# 7thCompetition_Send.net
KiCad netlist of a schematic drawn in Altium Designer
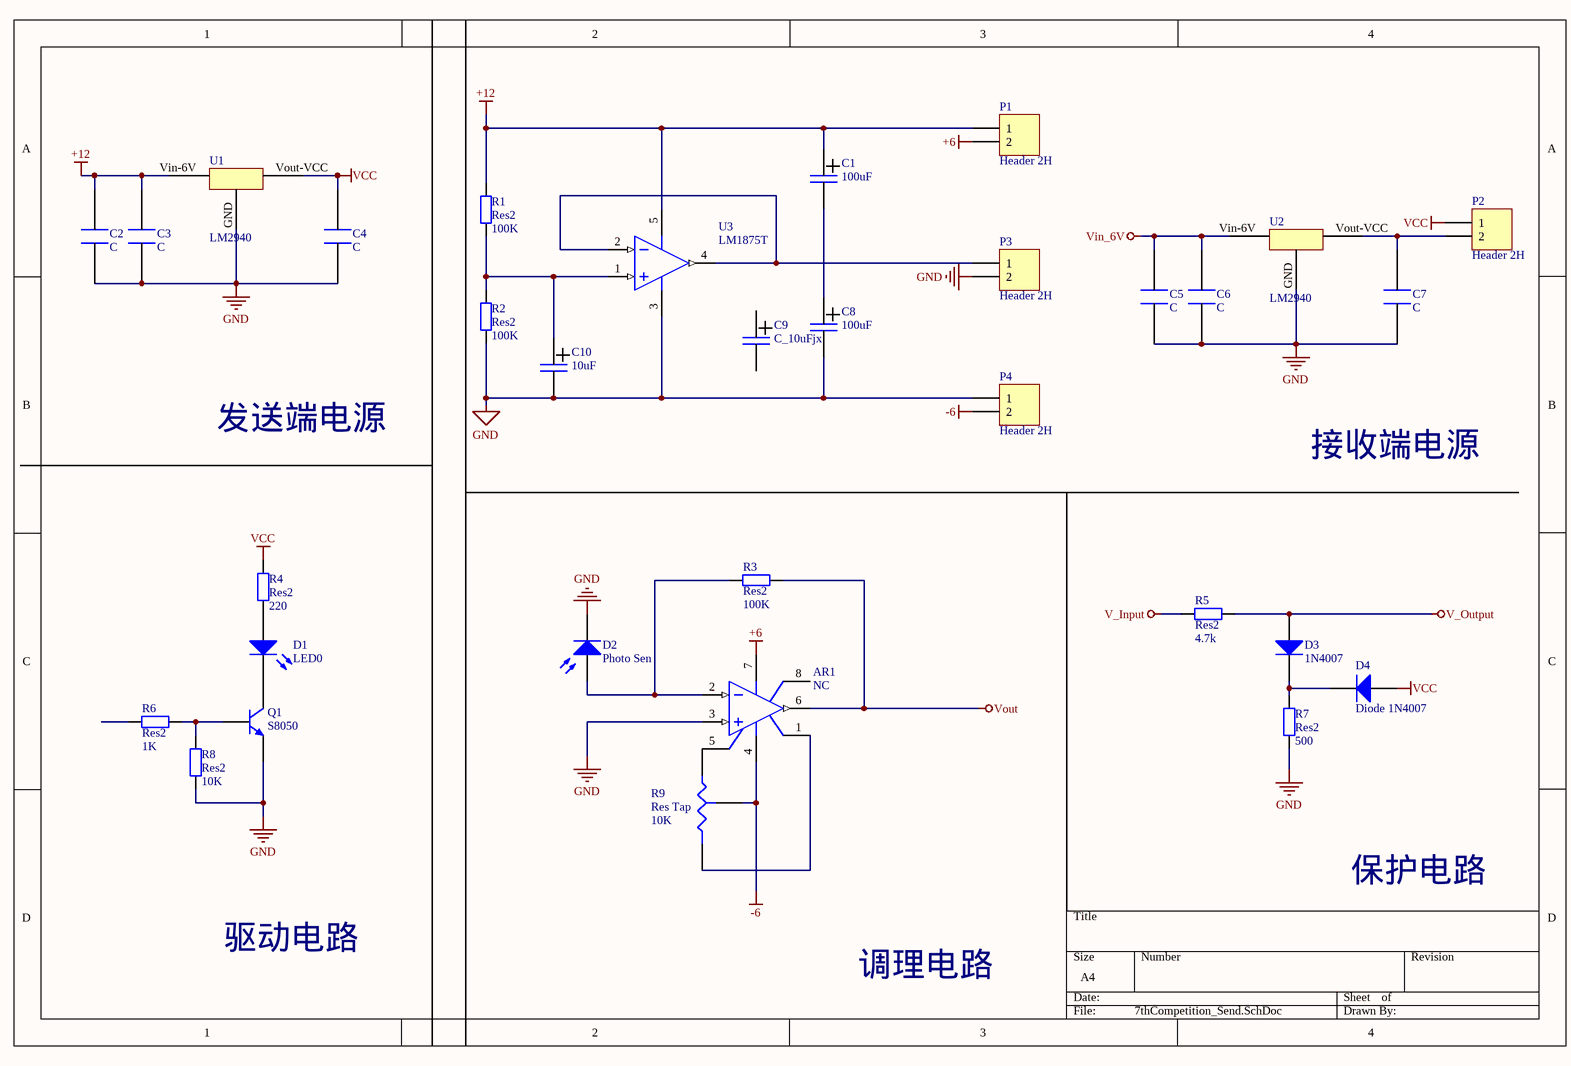
[diagram p0: 7thCompetition_Send.SchDoc]

(export (version "E")
  (design (tool "Eeschema 10.0.6"))
  (components
    (comp (ref "AR1")
      (value "NC")
      (footprint "H-08A")
      (description "FET Operational Amplifier")
      (fields (field (name "PUBLISHER") "Altium Limited"))
      (libsource (lib "Miscellaneous Devices") (part "Op Amp"))
    )
    (comp (ref "C1") (value "100uF") (footprint "C_10uFJX") (libsource (lib "常用库-Sniper") (part "C_10uFjx")))
    (comp (ref "C2") (value "C") (footprint "C") (libsource (lib "常用库-Sniper") (part "C")))
    (comp (ref "C3") (value "C") (footprint "C") (libsource (lib "常用库-Sniper") (part "C")))
    (comp (ref "C4") (value "C") (footprint "C") (libsource (lib "常用库-Sniper") (part "C")))
    (comp (ref "C5") (value "C") (footprint "C") (libsource (lib "常用库-Sniper") (part "C")))
    (comp (ref "C6") (value "C") (footprint "C") (libsource (lib "常用库-Sniper") (part "C")))
    (comp (ref "C7") (value "C") (footprint "C") (libsource (lib "常用库-Sniper") (part "C")))
    (comp (ref "C8") (value "100uF") (footprint "C_10uFJX") (libsource (lib "常用库-Sniper") (part "C_10uFjx")))
    (comp (ref "C9")
      (value "C_10uFjx")
      (footprint "C_10uFJX")
      (libsource (lib "常用库-Sniper") (part "C_10uFjx"))
    )
    (comp (ref "C10") (value "10uF") (footprint "C_10uFJX") (libsource (lib "常用库-Sniper") (part "C_10uFjx")))
    (comp (ref "D1")
      (value "LED0")
      (footprint "LED-0")
      (description "Typical INFRARED GaAs LED")
      (fields (field (name "PUBLISHER") "Altium Limited"))
      (libsource (lib "Miscellaneous Devices") (part "LED0"))
    )
    (comp (ref "D2")
      (value "Photo Sen")
      (footprint "PIN2")
      (description "Photosensitive Diode")
      (fields (field (name "PUBLISHER") "Altium Limited"))
      (libsource (lib "Miscellaneous Devices") (part "Photo Sen"))
    )
    (comp (ref "D3")
      (value "1N4007")
      (footprint "DO-41")
      (description "1 Amp General Purpose Rectifier")
      (fields (field (name "PUBLISHER") "Altium Limited"))
      (libsource (lib "Miscellaneous Devices") (part "Diode 1N4007"))
    )
    (comp (ref "D4")
      (value "Diode 1N4007")
      (footprint "DO-41")
      (description "1 Amp General Purpose Rectifier")
      (fields (field (name "PUBLISHER") "Altium Limited"))
      (libsource (lib "Miscellaneous Devices") (part "Diode 1N4007"))
    )
    (comp (ref "P1")
      (value "Header 2H")
      (footprint "HDR1X2H")
      (description "Header, 2-Pin, Right Angle")
      (fields (field (name "PUBLISHER") "Altium Limited"))
      (libsource (lib "Miscellaneous Connectors") (part "Header 2H"))
    )
    (comp (ref "P2")
      (value "Header 2H")
      (footprint "HDR1X2H")
      (description "Header, 2-Pin, Right Angle")
      (fields (field (name "PUBLISHER") "Altium Limited"))
      (libsource (lib "Miscellaneous Connectors") (part "Header 2H"))
    )
    (comp (ref "P3")
      (value "Header 2H")
      (footprint "HDR1X2H")
      (description "Header, 2-Pin, Right Angle")
      (fields (field (name "PUBLISHER") "Altium Limited"))
      (libsource (lib "Miscellaneous Connectors") (part "Header 2H"))
    )
    (comp (ref "P4")
      (value "Header 2H")
      (footprint "HDR1X2H")
      (description "Header, 2-Pin, Right Angle")
      (fields (field (name "PUBLISHER") "Altium Limited"))
      (libsource (lib "Miscellaneous Connectors") (part "Header 2H"))
    )
    (comp (ref "Q1")
      (value "S8050")
      (footprint "TO-92A")
      (description "NPN General Purpose Amplifier")
      (fields (field (name "PUBLISHER") "Altium Limited"))
      (libsource (lib "Miscellaneous Devices") (part "2N3904"))
    )
    (comp (ref "R1")
      (value "Res2")
      (footprint "AXIAL-0.4")
      (description "Resistor")
      (fields (field (name "ALTIUM_VALUE") "100K") (field (name "PUBLISHER") "Altium Limited"))
      (libsource (lib "") (part "Res2_1"))
    )
    (comp (ref "R2")
      (value "Res2")
      (footprint "AXIAL-0.4")
      (description "Resistor")
      (fields (field (name "ALTIUM_VALUE") "100K") (field (name "PUBLISHER") "Altium Limited"))
      (libsource (lib "") (part "Res2_1"))
    )
    (comp (ref "R3")
      (value "Res2")
      (footprint "AXIAL-0.4")
      (description "Resistor")
      (fields (field (name "ALTIUM_VALUE") "100K") (field (name "PUBLISHER") "Altium Limited"))
      (libsource (lib "Miscellaneous Devices") (part "Res2"))
    )
    (comp (ref "R4")
      (value "Res2")
      (footprint "AXIAL-0.4")
      (description "Resistor")
      (fields (field (name "ALTIUM_VALUE") "220") (field (name "PUBLISHER") "Altium Limited"))
      (libsource (lib "") (part "Res2_1"))
    )
    (comp (ref "R5")
      (value "Res2")
      (footprint "AXIAL-0.4")
      (description "Resistor")
      (fields (field (name "ALTIUM_VALUE") "4.7k") (field (name "PUBLISHER") "Altium Limited"))
      (libsource (lib "Miscellaneous Devices") (part "Res2"))
    )
    (comp (ref "R6")
      (value "Res2")
      (footprint "AXIAL-0.4")
      (description "Resistor")
      (fields (field (name "ALTIUM_VALUE") "1K") (field (name "PUBLISHER") "Altium Limited"))
      (libsource (lib "Miscellaneous Devices") (part "Res2"))
    )
    (comp (ref "R7")
      (value "Res2")
      (footprint "AXIAL-0.4")
      (description "Resistor")
      (fields (field (name "ALTIUM_VALUE") "500") (field (name "PUBLISHER") "Altium Limited"))
      (libsource (lib "") (part "Res2_1"))
    )
    (comp (ref "R8")
      (value "Res2")
      (footprint "AXIAL-0.4")
      (description "Resistor")
      (fields (field (name "ALTIUM_VALUE") "10K") (field (name "PUBLISHER") "Altium Limited"))
      (libsource (lib "") (part "Res2_1"))
    )
    (comp (ref "R9")
      (value "Res Tap")
      (footprint "VR3")
      (description "Tapped Resistor")
      (fields (field (name "ALTIUM_VALUE") "10K") (field (name "PUBLISHER") "Altium Limited"))
      (libsource (lib "Miscellaneous Devices") (part "Res Tap"))
    )
    (comp (ref "U1") (value "LM2940") (footprint "LM2940_DIP") (libsource (lib "常用库-Sniper") (part "LM2940")))
    (comp (ref "U2") (value "LM2940") (footprint "LM2940_DIP") (libsource (lib "常用库-Sniper") (part "LM2940")))
    (comp (ref "U3")
      (value "LM1875T")
      (footprint "TI-NDH5")
      (description "20 W Audio Power Amplifier, 0 to 70 degC, 5-pin FM (NDH5)")
      (fields (field (name "MANUFACTURER") "Texas Instruments"))
      (libsource (lib "TI Amplifiers and Linear Special Function Amplifier") (part "LM1875T"))
    )
  )
  (nets
    (net (code "1") (name "+6") (class "Default")
      (node (ref "AR1") (pin "7") (pinfunction "V+_7") (pintype "power_in"))
      (node (ref "P1") (pin "2") (pinfunction "2_2") (pintype "passive"))
    )
    (net (code "2") (name "+12") (class "Default")
      (node (ref "C1") (pin "1") (pinfunction "1_1") (pintype "passive"))
      (node (ref "C2") (pin "2") (pinfunction "2_2") (pintype "passive"))
      (node (ref "C3") (pin "1") (pinfunction "1_1") (pintype "passive"))
      (node (ref "P1") (pin "1") (pinfunction "1_1") (pintype "passive"))
      (node (ref "R1") (pin "2") (pinfunction "2_2") (pintype "passive"))
      (node (ref "U1") (pin "Vin-6V") (pinfunction "Vin_Vin-6V") (pintype "passive"))
      (node (ref "U3") (pin "5") (pinfunction "VCC_5") (pintype "power_in"))
    )
    (net (code "3") (name "-6") (class "Default")
      (node (ref "AR1") (pin "4") (pinfunction "V-_4") (pintype "power_in"))
      (node (ref "P4") (pin "2") (pinfunction "2_2") (pintype "passive"))
      (node (ref "R9") (pin "3") (pinfunction "TAP_3") (pintype "passive"))
    )
    (net (code "4") (name "GND") (class "Default")
      (node (ref "AR1") (pin "3") (pinfunction "IN+_3") (pintype "input"))
      (node (ref "C10") (pin "2") (pinfunction "2_2") (pintype "passive"))
      (node (ref "C2") (pin "1") (pinfunction "1_1") (pintype "passive"))
      (node (ref "C3") (pin "2") (pinfunction "2_2") (pintype "passive"))
      (node (ref "C4") (pin "1") (pinfunction "1_1") (pintype "passive"))
      (node (ref "C5") (pin "1") (pinfunction "1_1") (pintype "passive"))
      (node (ref "C6") (pin "2") (pinfunction "2_2") (pintype "passive"))
      (node (ref "C7") (pin "1") (pinfunction "1_1") (pintype "passive"))
      (node (ref "C8") (pin "2") (pinfunction "2_2") (pintype "passive"))
      (node (ref "D2") (pin "2") (pinfunction "K_2") (pintype "passive"))
      (node (ref "P3") (pin "2") (pinfunction "2_2") (pintype "passive"))
      (node (ref "P4") (pin "1") (pinfunction "1_1") (pintype "passive"))
      (node (ref "Q1") (pin "1") (pinfunction "E_1") (pintype "passive"))
      (node (ref "R2") (pin "1") (pinfunction "1_1") (pintype "passive"))
      (node (ref "R7") (pin "1") (pinfunction "1_1") (pintype "passive"))
      (node (ref "R8") (pin "1") (pinfunction "1_1") (pintype "passive"))
      (node (ref "U1") (pin "GND") (pinfunction "COM_GND") (pintype "passive"))
      (node (ref "U2") (pin "GND") (pinfunction "COM_GND") (pintype "passive"))
      (node (ref "U3") (pin "3") (pinfunction "VEE-_3") (pintype "power_in"))
    )
    (net (code "5") (name "Net-(AR1-IN-)") (class "Default")
      (node (ref "AR1") (pin "2") (pinfunction "IN-_2") (pintype "input"))
      (node (ref "D2") (pin "1") (pinfunction "A_1") (pintype "passive"))
      (node (ref "R3") (pin "1") (pinfunction "1_1") (pintype "passive"))
    )
    (net (code "6") (name "Net-(C1-Pad2)") (class "Default")
      (node (ref "C1") (pin "2") (pinfunction "2_2") (pintype "passive"))
      (node (ref "C8") (pin "1") (pinfunction "1_1") (pintype "passive"))
    )
    (net (code "7") (name "Net-(D1-A)") (class "Default")
      (node (ref "D1") (pin "1") (pinfunction "A_1") (pintype "passive"))
      (node (ref "R4") (pin "1") (pinfunction "1_1") (pintype "passive"))
    )
    (net (code "8") (name "Net-(D1-K)") (class "Default")
      (node (ref "D1") (pin "2") (pinfunction "K_2") (pintype "passive"))
      (node (ref "Q1") (pin "3") (pinfunction "C_3") (pintype "passive"))
    )
    (net (code "9") (name "Net-(D3-K)") (class "Default")
      (node (ref "D3") (pin "2") (pinfunction "K_2") (pintype "passive"))
      (node (ref "D4") (pin "2") (pinfunction "K_2") (pintype "passive"))
      (node (ref "R7") (pin "2") (pinfunction "2_2") (pintype "passive"))
    )
    (net (code "10") (name "Net-(Q1-B)") (class "Default")
      (node (ref "Q1") (pin "2") (pinfunction "B_2") (pintype "passive"))
      (node (ref "R6") (pin "2") (pinfunction "2_2") (pintype "passive"))
      (node (ref "R8") (pin "2") (pinfunction "2_2") (pintype "passive"))
    )
    (net (code "11") (name "Net-(R9-A)") (class "Default")
      (node (ref "AR1") (pin "5") (pinfunction "OS_NUL_5") (pintype "passive"))
      (node (ref "R9") (pin "1") (pinfunction "A_1") (pintype "passive"))
    )
    (net (code "12") (name "Net-(R9-B)") (class "Default")
      (node (ref "AR1") (pin "1") (pinfunction "OS_NUL_1") (pintype "passive"))
      (node (ref "R9") (pin "2") (pinfunction "B_2") (pintype "passive"))
    )
    (net (code "13") (name "Net-(U2-Vout)") (class "Default")
      (node (ref "C7") (pin "2") (pinfunction "2_2") (pintype "passive"))
      (node (ref "P2") (pin "2") (pinfunction "2_2") (pintype "passive"))
      (node (ref "U2") (pin "Vout-VCC") (pinfunction "Vout_Vout-VCC") (pintype "passive"))
    )
    (net (code "14") (name "Net-(U3-IN+)") (class "Default")
      (node (ref "C10") (pin "1") (pinfunction "1_1") (pintype "passive"))
      (node (ref "R1") (pin "1") (pinfunction "1_1") (pintype "passive"))
      (node (ref "R2") (pin "2") (pinfunction "2_2") (pintype "passive"))
      (node (ref "U3") (pin "1") (pinfunction "IN+_1") (pintype "input"))
    )
    (net (code "15") (name "Net-(U3-IN-)") (class "Default")
      (node (ref "P3") (pin "1") (pinfunction "1_1") (pintype "passive"))
      (node (ref "U3") (pin "2") (pinfunction "IN-_2") (pintype "input"))
      (node (ref "U3") (pin "4") (pinfunction "OUT_4") (pintype "output"))
    )
    (net (code "16") (name "VCC") (class "Default")
      (node (ref "C4") (pin "2") (pinfunction "2_2") (pintype "passive"))
      (node (ref "D4") (pin "1") (pinfunction "A_1") (pintype "passive"))
      (node (ref "P2") (pin "1") (pinfunction "1_1") (pintype "passive"))
      (node (ref "R4") (pin "2") (pinfunction "2_2") (pintype "passive"))
      (node (ref "U1") (pin "Vout-VCC") (pinfunction "Vout_Vout-VCC") (pintype "passive"))
    )
    (net (code "17") (name "V_Input") (class "Default")
      (node (ref "R5") (pin "1") (pinfunction "1_1") (pintype "passive"))
    )
    (net (code "18") (name "V_Output") (class "Default")
      (node (ref "D3") (pin "1") (pinfunction "A_1") (pintype "passive"))
      (node (ref "R5") (pin "2") (pinfunction "2_2") (pintype "passive"))
    )
    (net (code "19") (name "Vin_6V") (class "Default")
      (node (ref "C5") (pin "2") (pinfunction "2_2") (pintype "passive"))
      (node (ref "C6") (pin "1") (pinfunction "1_1") (pintype "passive"))
      (node (ref "U2") (pin "Vin-6V") (pinfunction "Vin_Vin-6V") (pintype "passive"))
    )
    (net (code "20") (name "Vout") (class "Default")
      (node (ref "AR1") (pin "6") (pinfunction "OUT_6") (pintype "output"))
      (node (ref "R3") (pin "2") (pinfunction "2_2") (pintype "passive"))
    )
    (net (code "21") (name "unconnected-(AR1-TAB-Pad8)") (class "Default")
      (node (ref "AR1") (pin "8") (pinfunction "TAB_8") (pintype "passive"))
    )
    (net (code "22") (name "unconnected-(C9-Pad1)") (class "Default")
      (node (ref "C9") (pin "1") (pinfunction "1_1") (pintype "passive"))
    )
    (net (code "23") (name "unconnected-(C9-Pad2)") (class "Default")
      (node (ref "C9") (pin "2") (pinfunction "2_2") (pintype "passive"))
    )
    (net (code "24") (name "unconnected-(R6-Pad1)") (class "Default")
      (node (ref "R6") (pin "1") (pinfunction "1_1") (pintype "passive"))
    )
  )
)
